# Schematic.net
KiCad netlist of a schematic drawn in Altium Designer
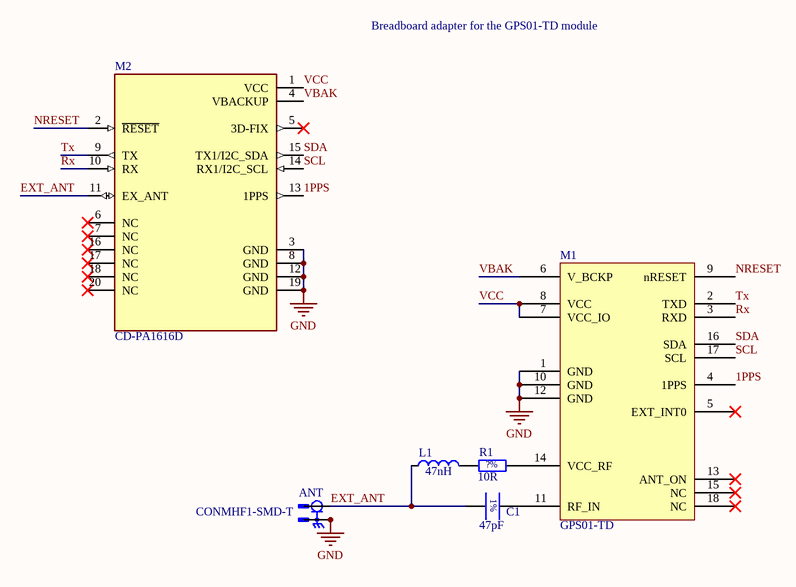
[diagram p0: Schematic.SchDoc]

(export (version "E")
  (design (tool "Eeschema 10.0.6"))
  (components
    (comp (ref "ANT")
      (value "CONMHF1-SMD-T")
      (footprint "TE_CONMHF1-SMD-T")
      (libsource (lib "CONMHF1-SMD-T") (part "CONMHF1-SMD-T"))
    )
    (comp (ref "C1")
      (value "47pF")
      (footprint "CAPACITOR_0805_2012M-70N")
      (description "Passive - Capacitor, Generic")
      (fields (field (name "TOLERANCE") "1%"))
      (libsource (lib "APSS Generic Components") (part "Generic Capacitor"))
    )
    (comp (ref "L1")
      (value "47nH")
      (footprint "APSS Generic Components:RESISTOR_0805_2012M-50N")
      (description "Passive - Inductor, Generic")
      (libsource (lib "APSS Generic Components") (part "Generic Inductor"))
    )
    (comp (ref "M1")
      (value "GPS01-TD")
      (footprint "GPS01-TD:GPS01-TD")
      (libsource (lib "GPS01-TD") (part "GPS01-TD"))
    )
    (comp (ref "M2")
      (value "CD-PA1616D")
      (footprint "XCVR_CD-PA1616D")
      (description "CD-PA1616DGNSS patch antenna module")
      (fields (field (name "MF") "CD Top"))
      (libsource (lib "CD-PA1616D") (part "CD-PA1616D"))
    )
    (comp (ref "R1")
      (value "10R")
      (footprint "RESISTOR_0805_2012M-50N")
      (description "Passive - Resistor, Generic")
      (fields (field (name "TOLERANCE") "?%"))
      (libsource (lib "APSS Generic Components") (part "Generic Resistor"))
    )
  )
  (nets
    (net (code "1") (name "/1PPS") (class "Default")
      (node (ref "M1") (pin "4") (pinfunction "1PPS_4") (pintype "passive"))
      (node (ref "M2") (pin "13") (pinfunction "1PPS_13") (pintype "output"))
    )
    (net (code "2") (name "/EXT_ANT") (class "Default")
      (node (ref "ANT") (pin "1") (pinfunction "SIG_1") (pintype "passive"))
      (node (ref "C1") (pin "1") (pinfunction "1_1") (pintype "passive"))
      (node (ref "L1") (pin "1") (pinfunction "1_1") (pintype "passive"))
      (node (ref "M2") (pin "11") (pinfunction "EX_ANT_11") (pintype "bidirectional"))
    )
    (net (code "3") (name "/NRESET") (class "Default")
      (node (ref "M1") (pin "9") (pinfunction "nRESET_9") (pintype "passive"))
      (node (ref "M2") (pin "2") (pinfunction "~{RESET}_2") (pintype "input"))
    )
    (net (code "4") (name "/Rx") (class "Default")
      (node (ref "M1") (pin "3") (pinfunction "RXD_3") (pintype "passive"))
      (node (ref "M2") (pin "10") (pinfunction "RX_10") (pintype "input"))
    )
    (net (code "5") (name "/SCL") (class "Default")
      (node (ref "M1") (pin "17") (pinfunction "SCL_17") (pintype "passive"))
      (node (ref "M2") (pin "14") (pinfunction "RX1/I2C_SCL_14") (pintype "input"))
    )
    (net (code "6") (name "/SDA") (class "Default")
      (node (ref "M1") (pin "16") (pinfunction "SDA_16") (pintype "passive"))
      (node (ref "M2") (pin "15") (pinfunction "TX1/I2C_SDA_15") (pintype "output"))
    )
    (net (code "7") (name "/Tx") (class "Default")
      (node (ref "M1") (pin "2") (pinfunction "TXD_2") (pintype "passive"))
      (node (ref "M2") (pin "9") (pinfunction "TX_9") (pintype "output"))
    )
    (net (code "8") (name "/VBAK") (class "Default")
      (node (ref "M1") (pin "6") (pinfunction "V_BCKP_6") (pintype "passive"))
      (node (ref "M2") (pin "4") (pinfunction "VBACKUP_4") (pintype "power_in"))
    )
    (net (code "9") (name "/VCC") (class "Default")
      (node (ref "M1") (pin "7") (pinfunction "VCC_IO_7") (pintype "passive"))
      (node (ref "M1") (pin "8") (pinfunction "VCC_8") (pintype "passive"))
      (node (ref "M2") (pin "1") (pinfunction "VCC_1") (pintype "power_in"))
    )
    (net (code "10") (name "GND") (class "Default")
      (node (ref "ANT") (pin "2") (pinfunction "GND_2") (pintype "power_in"))
      (node (ref "ANT") (pin "3") (pinfunction "GND_3") (pintype "power_in"))
      (node (ref "ANT") (pin "4") (pinfunction "GND_4") (pintype "power_in"))
      (node (ref "M1") (pin "1") (pinfunction "GND_1") (pintype "passive"))
      (node (ref "M1") (pin "10") (pinfunction "GND_10") (pintype "passive"))
      (node (ref "M1") (pin "12") (pinfunction "GND_12") (pintype "passive"))
      (node (ref "M2") (pin "12") (pinfunction "GND_12") (pintype "power_in"))
      (node (ref "M2") (pin "19") (pinfunction "GND_19") (pintype "power_in"))
      (node (ref "M2") (pin "3") (pinfunction "GND_3") (pintype "power_in"))
      (node (ref "M2") (pin "8") (pinfunction "GND_8") (pintype "power_in"))
    )
    (net (code "11") (name "Net-(L1-Pad2)") (class "Default")
      (node (ref "L1") (pin "2") (pinfunction "2_2") (pintype "passive"))
      (node (ref "R1") (pin "1") (pinfunction "1_1") (pintype "passive"))
    )
    (net (code "12") (name "Net-(M1-RF_IN)") (class "Default")
      (node (ref "C1") (pin "2") (pinfunction "2_2") (pintype "passive"))
      (node (ref "M1") (pin "11") (pinfunction "RF_IN_11") (pintype "passive"))
    )
    (net (code "13") (name "Net-(M1-VCC_RF)") (class "Default")
      (node (ref "M1") (pin "14") (pinfunction "VCC_RF_14") (pintype "passive"))
      (node (ref "R1") (pin "2") (pinfunction "2_2") (pintype "passive"))
    )
    (net (code "14") (name "unconnected-(M1-ANT_ON-Pad13)") (class "Default")
      (node (ref "M1") (pin "13") (pinfunction "ANT_ON_13") (pintype "passive+no_connect"))
    )
    (net (code "15") (name "unconnected-(M1-EXT_INT0-Pad5)") (class "Default")
      (node (ref "M1") (pin "5") (pinfunction "EXT_INT0_5") (pintype "passive+no_connect"))
    )
    (net (code "16") (name "unconnected-(M1-NC-Pad15)") (class "Default")
      (node (ref "M1") (pin "15") (pinfunction "NC_15") (pintype "passive+no_connect"))
    )
    (net (code "17") (name "unconnected-(M1-NC-Pad18)") (class "Default")
      (node (ref "M1") (pin "18") (pinfunction "NC_18") (pintype "passive+no_connect"))
    )
    (net (code "18") (name "unconnected-(M2-3D-FIX-Pad5)") (class "Default")
      (node (ref "M2") (pin "5") (pinfunction "3D-FIX_5") (pintype "output+no_connect"))
    )
    (net (code "19") (name "unconnected-(M2-NC-Pad6)") (class "Default")
      (node (ref "M2") (pin "6") (pinfunction "NC_6") (pintype "passive+no_connect"))
    )
    (net (code "20") (name "unconnected-(M2-NC-Pad7)") (class "Default")
      (node (ref "M2") (pin "7") (pinfunction "NC_7") (pintype "passive+no_connect"))
    )
    (net (code "21") (name "unconnected-(M2-NC-Pad16)") (class "Default")
      (node (ref "M2") (pin "16") (pinfunction "NC_16") (pintype "passive+no_connect"))
    )
    (net (code "22") (name "unconnected-(M2-NC-Pad17)") (class "Default")
      (node (ref "M2") (pin "17") (pinfunction "NC_17") (pintype "passive+no_connect"))
    )
    (net (code "23") (name "unconnected-(M2-NC-Pad18)") (class "Default")
      (node (ref "M2") (pin "18") (pinfunction "NC_18") (pintype "passive+no_connect"))
    )
    (net (code "24") (name "unconnected-(M2-NC-Pad20)") (class "Default")
      (node (ref "M2") (pin "20") (pinfunction "NC_20") (pintype "passive+no_connect"))
    )
  )
)
